# atividade-02.net
KiCad netlist of a schematic drawn in EAGLE
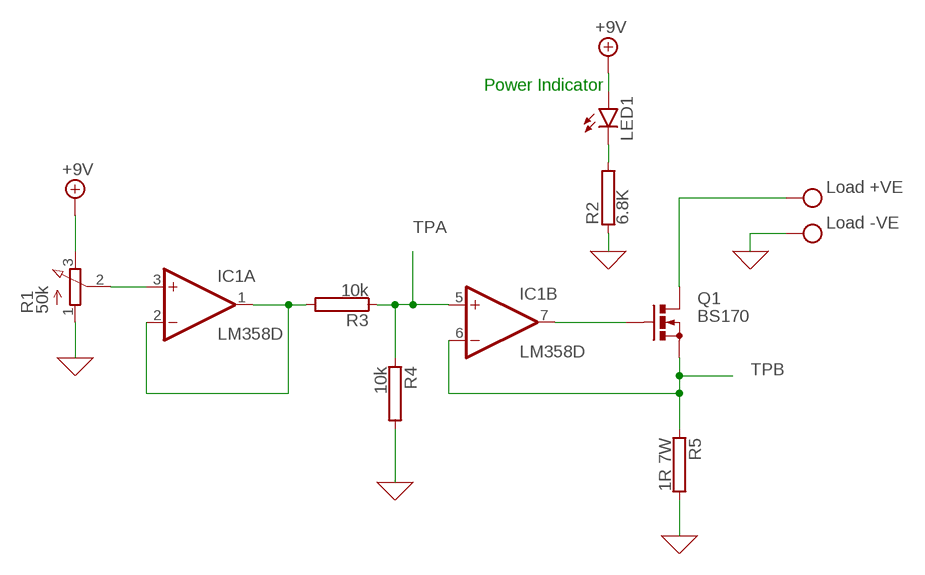
[diagram p0: schematic, sheet 1]

(export (version "E")
  (design (tool "Eeschema 10.0.6"))
  (components
    (comp (ref "IC1")
      (value "LM358D")
      (footprint "eagle-import:SO08")
      (libsource (lib "eagle-import") (part "LM358D"))
    )
    (comp (ref "LED1")
      (value "LED3MM")
      (footprint "eagle-import:LED3MM")
      (libsource (lib "eagle-import") (part "LED3MM"))
    )
    (comp (ref "Q1")
      (value "BS170")
      (footprint "eagle-import:SOT54E")
      (libsource (lib "eagle-import") (part "BS170"))
    )
    (comp (ref "R1")
      (value "50k")
      (footprint "eagle-import:3RP_1610N")
      (libsource (lib "eagle-import") (part "3RP/1610N"))
    )
    (comp (ref "R2")
      (value "6.8K")
      (footprint "eagle-import:AC01")
      (libsource (lib "eagle-import") (part "RAC01"))
    )
    (comp (ref "R3")
      (value "10k")
      (footprint "eagle-import:AC01")
      (libsource (lib "eagle-import") (part "RAC01"))
    )
    (comp (ref "R4")
      (value "10k")
      (footprint "eagle-import:AC01")
      (libsource (lib "eagle-import") (part "RAC01"))
    )
    (comp (ref "R5")
      (value "1R 7W")
      (footprint "eagle-import:AC01")
      (libsource (lib "eagle-import") (part "RAC01"))
    )
  )
  (nets
    (net (code "1") (name "+9V") (class "Default")
      (node (ref "LED1") (pin "A") (pinfunction "A_A") (pintype "passive"))
      (node (ref "R1") (pin "3") (pinfunction "E_3") (pintype "passive"))
    )
    (net (code "2") (name "/TPA") (class "Default")
      (node (ref "IC1") (pin "5") (pinfunction "+IN_5") (pintype "input"))
      (node (ref "R3") (pin "1") (pinfunction "1_1") (pintype "passive"))
      (node (ref "R4") (pin "1") (pinfunction "1_1") (pintype "passive"))
    )
    (net (code "3") (name "/TPB") (class "Default")
      (node (ref "IC1") (pin "6") (pinfunction "-IN_6") (pintype "input"))
      (node (ref "Q1") (pin "S") (pinfunction "S_S") (pintype "passive"))
      (node (ref "R5") (pin "1") (pinfunction "1_1") (pintype "passive"))
    )
    (net (code "4") (name "GND") (class "Default")
      (node (ref "R1") (pin "1") (pinfunction "A_1") (pintype "passive"))
      (node (ref "R2") (pin "1") (pinfunction "1_1") (pintype "passive"))
      (node (ref "R4") (pin "2") (pinfunction "2_2") (pintype "passive"))
      (node (ref "R5") (pin "2") (pinfunction "2_2") (pintype "passive"))
    )
    (net (code "5") (name "Load +VE") (class "Default")
      (node (ref "Q1") (pin "D") (pinfunction "D_D") (pintype "passive"))
    )
    (net (code "6") (name "Net-(IC1A-+IN)") (class "Default")
      (node (ref "IC1") (pin "3") (pinfunction "+IN_3") (pintype "input"))
      (node (ref "R1") (pin "2") (pinfunction "S_2") (pintype "passive"))
    )
    (net (code "7") (name "Net-(IC1A--IN)") (class "Default")
      (node (ref "IC1") (pin "1") (pinfunction "OUT_1") (pintype "output"))
      (node (ref "IC1") (pin "2") (pinfunction "-IN_2") (pintype "input"))
      (node (ref "R3") (pin "2") (pinfunction "2_2") (pintype "passive"))
    )
    (net (code "8") (name "Net-(IC1B-OUT)") (class "Default")
      (node (ref "IC1") (pin "7") (pinfunction "OUT_7") (pintype "output"))
      (node (ref "Q1") (pin "G") (pinfunction "G_G") (pintype "passive"))
    )
    (net (code "9") (name "Net-(LED1-C)") (class "Default")
      (node (ref "LED1") (pin "K") (pinfunction "C_K") (pintype "passive"))
      (node (ref "R2") (pin "2") (pinfunction "2_2") (pintype "passive"))
    )
  )
)
